# Macro_Pad.net
KiCad netlist of a schematic drawn in EasyEDA Pro
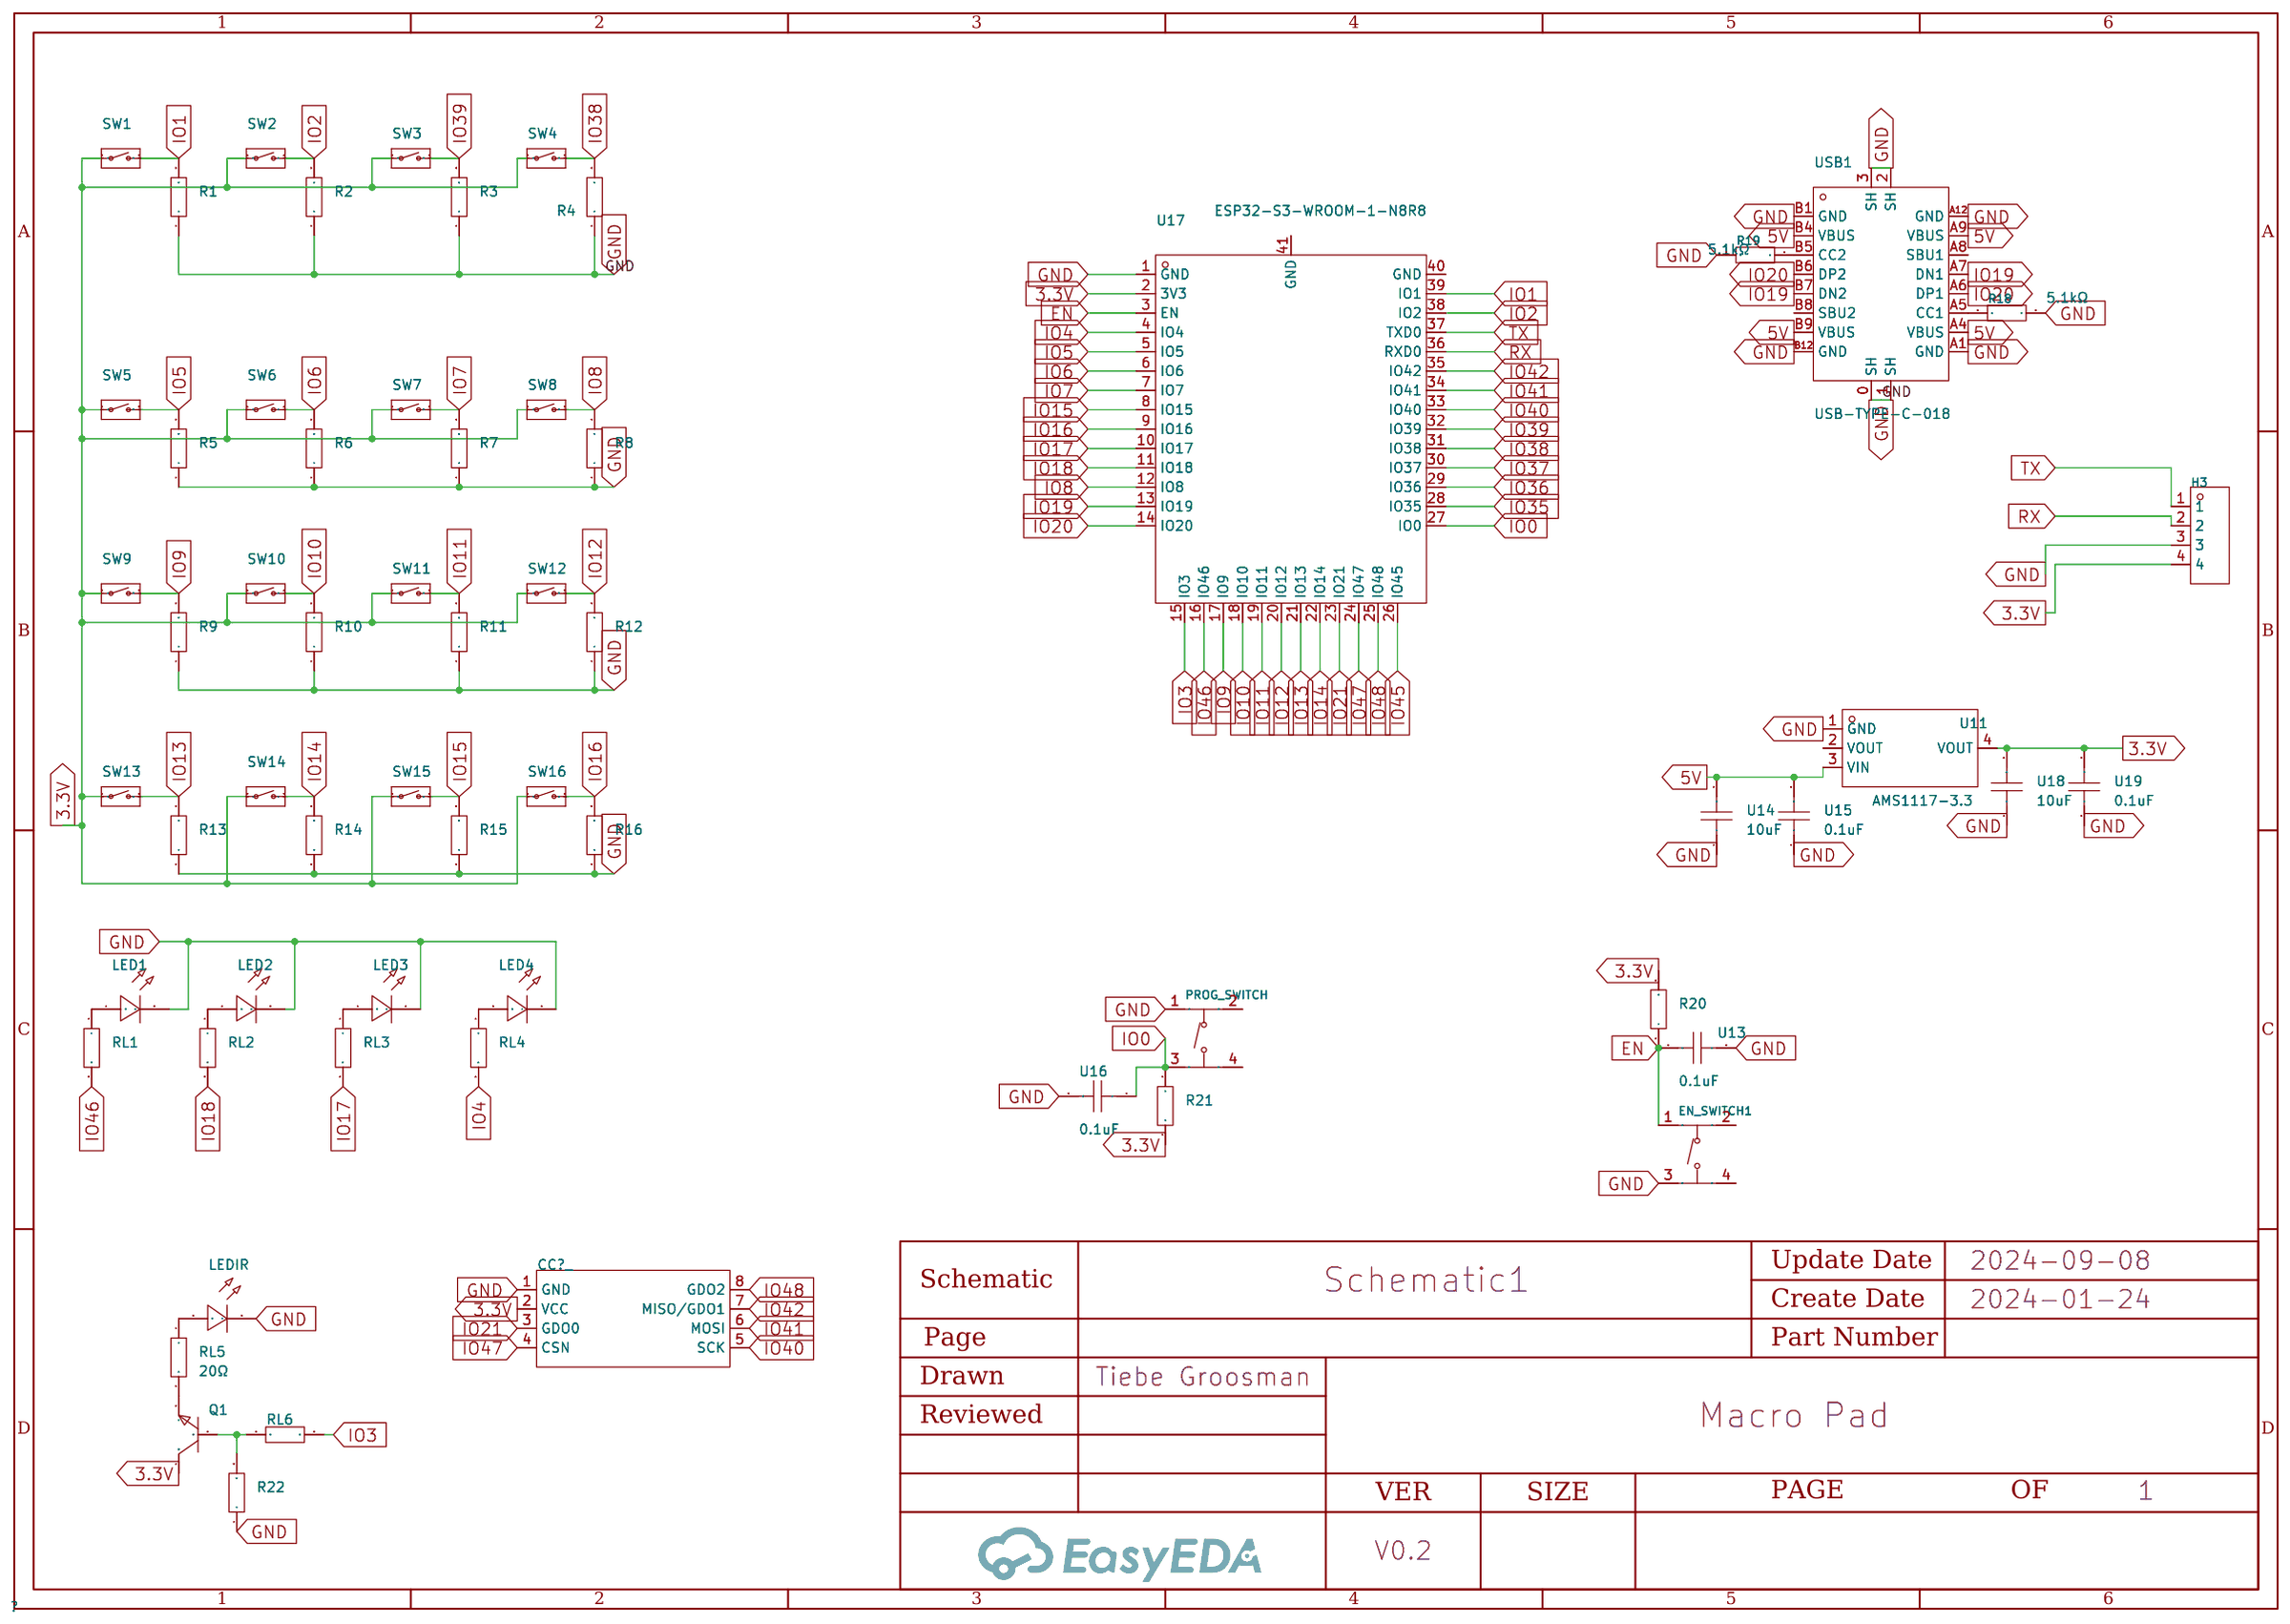
[diagram p0: schematic sheet]

(export (version "E")
  (design (tool "Eeschema 10.0.6"))
  (components
    (comp (ref "CC?_")
      (value "~")
      (footprint "easyedapro:CC1101-BOARS")
      (libsource (lib "easyedapro") (part "CC1101 Module"))
    )
    (comp (ref "EN_SWITCH1")
      (value "TS-1187A-B-A-B")
      (footprint "easyedapro:SW-SMD_4P-L5.1-W5.1-P3.70-LS6.5-TL-2")
      (fields (field (name "Manufacturer") "XKB Connectivity(中国星坤)"))
      (libsource (lib "easyedapro") (part "TS-1187A-B-A-B"))
    )
    (comp (ref "H3")
      (value "~")
      (footprint "easyedapro:HDR-TH_4P-P2.54-V-M")
      (libsource (lib "easyedapro") (part "PZ254V-11-04P"))
    )
    (comp (ref "LED1")
      (value "~")
      (footprint "easyedapro:LED-TH_BD3.0-P2.54-FD")
      (libsource (lib "easyedapro") (part "LED_TH-R"))
    )
    (comp (ref "LED2")
      (value "~")
      (footprint "easyedapro:LED-TH_BD3.0-P2.54-FD")
      (libsource (lib "easyedapro") (part "LED_TH-R"))
    )
    (comp (ref "LED3")
      (value "~")
      (footprint "easyedapro:LED-TH_BD3.0-P2.54-FD")
      (libsource (lib "easyedapro") (part "LED_TH-R"))
    )
    (comp (ref "LED4")
      (value "~")
      (footprint "easyedapro:LED-TH_BD3.0-P2.54-FD")
      (libsource (lib "easyedapro") (part "LED_TH-R"))
    )
    (comp (ref "LEDIR")
      (value "~")
      (footprint "easyedapro:LED-TH_BD3.0-P2.54-FD")
      (libsource (lib "easyedapro") (part "LED_TH-R"))
    )
    (comp (ref "PROG_SWITCH")
      (value "TS-1187A-B-A-B")
      (footprint "easyedapro:SW-SMD_4P-L5.1-W5.1-P3.70-LS6.5-TL-2")
      (fields (field (name "Manufacturer") "XKB Connectivity(中国星坤)"))
      (libsource (lib "easyedapro") (part "TS-1187A-B-A-B"))
    )
    (comp (ref "Q1")
      (value "~")
      (footprint "easyedapro:SOT-23_L2.9-W1.3-P1.90-LS2.4-BR")
      (libsource (lib "easyedapro") (part "NPN"))
    )
    (comp (ref "R1")
      (value "10.2kΩ")
      (footprint "easyedapro:R0402")
      (fields
        (field (name "Manufacturer Part") "0402WGF1022TCE")
        (field (name "Manufacturer") "UNI-ROYAL(厚声)")
      )
      (libsource (lib "easyedapro") (part "0402WGF1022TCE"))
    )
    (comp (ref "R2")
      (value "10.2kΩ")
      (footprint "easyedapro:R0402")
      (fields
        (field (name "Manufacturer Part") "0402WGF1022TCE")
        (field (name "Manufacturer") "UNI-ROYAL(厚声)")
      )
      (libsource (lib "easyedapro") (part "0402WGF1022TCE"))
    )
    (comp (ref "R3")
      (value "10.2kΩ")
      (footprint "easyedapro:R0402")
      (fields
        (field (name "Manufacturer Part") "0402WGF1022TCE")
        (field (name "Manufacturer") "UNI-ROYAL(厚声)")
      )
      (libsource (lib "easyedapro") (part "0402WGF1022TCE"))
    )
    (comp (ref "R4")
      (value "10.2kΩ")
      (footprint "easyedapro:R0402")
      (fields
        (field (name "Manufacturer Part") "0402WGF1022TCE")
        (field (name "Manufacturer") "UNI-ROYAL(厚声)")
      )
      (libsource (lib "easyedapro") (part "0402WGF1022TCE"))
    )
    (comp (ref "R5")
      (value "10.2kΩ")
      (footprint "easyedapro:R0402")
      (fields
        (field (name "Manufacturer Part") "0402WGF1022TCE")
        (field (name "Manufacturer") "UNI-ROYAL(厚声)")
      )
      (libsource (lib "easyedapro") (part "0402WGF1022TCE"))
    )
    (comp (ref "R6")
      (value "10.2kΩ")
      (footprint "easyedapro:R0402")
      (fields
        (field (name "Manufacturer Part") "0402WGF1022TCE")
        (field (name "Manufacturer") "UNI-ROYAL(厚声)")
      )
      (libsource (lib "easyedapro") (part "0402WGF1022TCE"))
    )
    (comp (ref "R7")
      (value "10.2kΩ")
      (footprint "easyedapro:R0402")
      (fields
        (field (name "Manufacturer Part") "0402WGF1022TCE")
        (field (name "Manufacturer") "UNI-ROYAL(厚声)")
      )
      (libsource (lib "easyedapro") (part "0402WGF1022TCE"))
    )
    (comp (ref "R8")
      (value "10.2kΩ")
      (footprint "easyedapro:R0402")
      (fields
        (field (name "Manufacturer Part") "0402WGF1022TCE")
        (field (name "Manufacturer") "UNI-ROYAL(厚声)")
      )
      (libsource (lib "easyedapro") (part "0402WGF1022TCE"))
    )
    (comp (ref "R9")
      (value "10.2kΩ")
      (footprint "easyedapro:R0402")
      (fields
        (field (name "Manufacturer Part") "0402WGF1022TCE")
        (field (name "Manufacturer") "UNI-ROYAL(厚声)")
      )
      (libsource (lib "easyedapro") (part "0402WGF1022TCE"))
    )
    (comp (ref "R10")
      (value "10.2kΩ")
      (footprint "easyedapro:R0402")
      (fields
        (field (name "Manufacturer Part") "0402WGF1022TCE")
        (field (name "Manufacturer") "UNI-ROYAL(厚声)")
      )
      (libsource (lib "easyedapro") (part "0402WGF1022TCE"))
    )
    (comp (ref "R11")
      (value "10.2kΩ")
      (footprint "easyedapro:R0402")
      (fields
        (field (name "Manufacturer Part") "0402WGF1022TCE")
        (field (name "Manufacturer") "UNI-ROYAL(厚声)")
      )
      (libsource (lib "easyedapro") (part "0402WGF1022TCE"))
    )
    (comp (ref "R12")
      (value "10.2kΩ")
      (footprint "easyedapro:R0402")
      (fields
        (field (name "Manufacturer Part") "0402WGF1022TCE")
        (field (name "Manufacturer") "UNI-ROYAL(厚声)")
      )
      (libsource (lib "easyedapro") (part "0402WGF1022TCE"))
    )
    (comp (ref "R13")
      (value "10.2kΩ")
      (footprint "easyedapro:R0402")
      (fields
        (field (name "Manufacturer Part") "0402WGF1022TCE")
        (field (name "Manufacturer") "UNI-ROYAL(厚声)")
      )
      (libsource (lib "easyedapro") (part "0402WGF1022TCE"))
    )
    (comp (ref "R14")
      (value "10.2kΩ")
      (footprint "easyedapro:R0402")
      (fields
        (field (name "Manufacturer Part") "0402WGF1022TCE")
        (field (name "Manufacturer") "UNI-ROYAL(厚声)")
      )
      (libsource (lib "easyedapro") (part "0402WGF1022TCE"))
    )
    (comp (ref "R15")
      (value "10.2kΩ")
      (footprint "easyedapro:R0402")
      (fields
        (field (name "Manufacturer Part") "0402WGF1022TCE")
        (field (name "Manufacturer") "UNI-ROYAL(厚声)")
      )
      (libsource (lib "easyedapro") (part "0402WGF1022TCE"))
    )
    (comp (ref "R16")
      (value "10.2kΩ")
      (footprint "easyedapro:R0402")
      (fields
        (field (name "Manufacturer Part") "0402WGF1022TCE")
        (field (name "Manufacturer") "UNI-ROYAL(厚声)")
      )
      (libsource (lib "easyedapro") (part "0402WGF1022TCE"))
    )
    (comp (ref "R18")
      (value "5.1kΩ")
      (footprint "easyedapro:R0402")
      (fields (field (name "Manufacturer Part") "SCR1210J5K1") (field (name "Manufacturer") "VO(翔胜)"))
      (libsource (lib "easyedapro") (part "0402WGJ0512TCE"))
    )
    (comp (ref "R19")
      (value "5.1kΩ")
      (footprint "easyedapro:R0402")
      (fields (field (name "Manufacturer Part") "SCR1210J5K1") (field (name "Manufacturer") "VO(翔胜)"))
      (libsource (lib "easyedapro") (part "0402WGJ0512TCE"))
    )
    (comp (ref "R20")
      (value "10.2kΩ")
      (footprint "easyedapro:R0402")
      (fields
        (field (name "Manufacturer Part") "0402WGF1022TCE")
        (field (name "Manufacturer") "UNI-ROYAL(厚声)")
      )
      (libsource (lib "easyedapro") (part "0402WGF1022TCE"))
    )
    (comp (ref "R21")
      (value "10.2kΩ")
      (footprint "easyedapro:R0402")
      (fields
        (field (name "Manufacturer Part") "0402WGF1022TCE")
        (field (name "Manufacturer") "UNI-ROYAL(厚声)")
      )
      (libsource (lib "easyedapro") (part "0402WGF1022TCE"))
    )
    (comp (ref "R22")
      (value "10.2kΩ")
      (footprint "easyedapro:R0402")
      (fields
        (field (name "Manufacturer Part") "0402WGF1022TCE")
        (field (name "Manufacturer") "UNI-ROYAL(厚声)")
      )
      (libsource (lib "easyedapro") (part "0402WGF1022TCE"))
    )
    (comp (ref "RL1")
      (value "330Ω")
      (footprint "easyedapro:R0402")
      (fields
        (field (name "Manufacturer Part") "0402WGJ0331TCE")
        (field (name "Manufacturer") "UNI-ROYAL(厚声)")
      )
      (libsource (lib "easyedapro") (part "0402WGJ0331TCE"))
    )
    (comp (ref "RL2")
      (value "330Ω")
      (footprint "easyedapro:R0402")
      (fields
        (field (name "Manufacturer Part") "0402WGJ0331TCE")
        (field (name "Manufacturer") "UNI-ROYAL(厚声)")
      )
      (libsource (lib "easyedapro") (part "0402WGJ0331TCE"))
    )
    (comp (ref "RL3")
      (value "330Ω")
      (footprint "easyedapro:R0402")
      (fields
        (field (name "Manufacturer Part") "0402WGJ0331TCE")
        (field (name "Manufacturer") "UNI-ROYAL(厚声)")
      )
      (libsource (lib "easyedapro") (part "0402WGJ0331TCE"))
    )
    (comp (ref "RL4")
      (value "330Ω")
      (footprint "easyedapro:R0402")
      (fields
        (field (name "Manufacturer Part") "0402WGJ0331TCE")
        (field (name "Manufacturer") "UNI-ROYAL(厚声)")
      )
      (libsource (lib "easyedapro") (part "0402WGJ0331TCE"))
    )
    (comp (ref "RL5")
      (value "20Ω")
      (footprint "easyedapro:R0402")
      (fields
        (field (name "Manufacturer Part") "0402WGJ0331TCE")
        (field (name "Manufacturer") "UNI-ROYAL(厚声)")
      )
      (libsource (lib "easyedapro") (part "0402WGJ0331TCE"))
    )
    (comp (ref "RL6")
      (value "330Ω")
      (footprint "easyedapro:R0402")
      (fields
        (field (name "Manufacturer Part") "0402WGJ0331TCE")
        (field (name "Manufacturer") "UNI-ROYAL(厚声)")
      )
      (libsource (lib "easyedapro") (part "0402WGJ0331TCE"))
    )
    (comp (ref "SW1")
      (value "CHERRY-MX-LED")
      (footprint "easyedapro:CHERRYMX")
      (fields (field (name "Manufacturer Part") "Cherry MX Green") (field (name "Manufacturer") "Cherry"))
      (libsource (lib "easyedapro") (part "CHERRY-MX-LED"))
    )
    (comp (ref "SW2")
      (value "CHERRY-MX-LED")
      (footprint "easyedapro:CHERRYMX")
      (fields (field (name "Manufacturer Part") "Cherry MX Green") (field (name "Manufacturer") "Cherry"))
      (libsource (lib "easyedapro") (part "CHERRY-MX-LED"))
    )
    (comp (ref "SW3")
      (value "CHERRY-MX-LED")
      (footprint "easyedapro:CHERRYMX")
      (fields (field (name "Manufacturer Part") "Cherry MX Green") (field (name "Manufacturer") "Cherry"))
      (libsource (lib "easyedapro") (part "CHERRY-MX-LED"))
    )
    (comp (ref "SW4")
      (value "CHERRY-MX-LED")
      (footprint "easyedapro:CHERRYMX")
      (fields (field (name "Manufacturer Part") "Cherry MX Green") (field (name "Manufacturer") "Cherry"))
      (libsource (lib "easyedapro") (part "CHERRY-MX-LED"))
    )
    (comp (ref "SW5")
      (value "CHERRY-MX-LED")
      (footprint "easyedapro:CHERRYMX")
      (fields (field (name "Manufacturer Part") "Cherry MX Green") (field (name "Manufacturer") "Cherry"))
      (libsource (lib "easyedapro") (part "CHERRY-MX-LED"))
    )
    (comp (ref "SW6")
      (value "CHERRY-MX-LED")
      (footprint "easyedapro:CHERRYMX")
      (fields (field (name "Manufacturer Part") "Cherry MX Green") (field (name "Manufacturer") "Cherry"))
      (libsource (lib "easyedapro") (part "CHERRY-MX-LED"))
    )
    (comp (ref "SW7")
      (value "CHERRY-MX-LED")
      (footprint "easyedapro:CHERRYMX")
      (fields (field (name "Manufacturer Part") "Cherry MX Green") (field (name "Manufacturer") "Cherry"))
      (libsource (lib "easyedapro") (part "CHERRY-MX-LED"))
    )
    (comp (ref "SW8")
      (value "CHERRY-MX-LED")
      (footprint "easyedapro:CHERRYMX")
      (fields (field (name "Manufacturer Part") "Cherry MX Green") (field (name "Manufacturer") "Cherry"))
      (libsource (lib "easyedapro") (part "CHERRY-MX-LED"))
    )
    (comp (ref "SW9")
      (value "CHERRY-MX-LED")
      (footprint "easyedapro:CHERRYMX")
      (fields (field (name "Manufacturer Part") "Cherry MX Green") (field (name "Manufacturer") "Cherry"))
      (libsource (lib "easyedapro") (part "CHERRY-MX-LED"))
    )
    (comp (ref "SW10")
      (value "CHERRY-MX-LED")
      (footprint "easyedapro:CHERRYMX")
      (fields (field (name "Manufacturer Part") "Cherry MX Green") (field (name "Manufacturer") "Cherry"))
      (libsource (lib "easyedapro") (part "CHERRY-MX-LED"))
    )
    (comp (ref "SW11")
      (value "CHERRY-MX-LED")
      (footprint "easyedapro:CHERRYMX")
      (fields (field (name "Manufacturer Part") "Cherry MX Green") (field (name "Manufacturer") "Cherry"))
      (libsource (lib "easyedapro") (part "CHERRY-MX-LED"))
    )
    (comp (ref "SW12")
      (value "CHERRY-MX-LED")
      (footprint "easyedapro:CHERRYMX")
      (fields (field (name "Manufacturer Part") "Cherry MX Green") (field (name "Manufacturer") "Cherry"))
      (libsource (lib "easyedapro") (part "CHERRY-MX-LED"))
    )
    (comp (ref "SW13")
      (value "CHERRY-MX-LED")
      (footprint "easyedapro:CHERRYMX")
      (fields (field (name "Manufacturer Part") "Cherry MX Green") (field (name "Manufacturer") "Cherry"))
      (libsource (lib "easyedapro") (part "CHERRY-MX-LED"))
    )
    (comp (ref "SW14")
      (value "CHERRY-MX-LED")
      (footprint "easyedapro:CHERRYMX")
      (fields (field (name "Manufacturer Part") "Cherry MX Green") (field (name "Manufacturer") "Cherry"))
      (libsource (lib "easyedapro") (part "CHERRY-MX-LED"))
    )
    (comp (ref "SW15")
      (value "CHERRY-MX-LED")
      (footprint "easyedapro:CHERRYMX")
      (fields (field (name "Manufacturer Part") "Cherry MX Green") (field (name "Manufacturer") "Cherry"))
      (libsource (lib "easyedapro") (part "CHERRY-MX-LED"))
    )
    (comp (ref "SW16")
      (value "CHERRY-MX-LED")
      (footprint "easyedapro:CHERRYMX")
      (fields (field (name "Manufacturer Part") "Cherry MX Green") (field (name "Manufacturer") "Cherry"))
      (libsource (lib "easyedapro") (part "CHERRY-MX-LED"))
    )
    (comp (ref "U11")
      (value "AMS1117-3.3")
      (footprint "easyedapro:SOT-223-3_L6.5-W3.4-P2.30-LS7.0-BR")
      (fields (field (name "Manufacturer") "AMS"))
      (libsource (lib "easyedapro") (part "AMS1117-3.3"))
    )
    (comp (ref "U13")
      (value "0.1uF")
      (footprint "easyedapro:C0402")
      (fields
        (field (name "Manufacturer Part") "CC1210KKX7R9BB105")
        (field (name "Manufacturer") "YAGEO(国巨)")
      )
      (libsource (lib "easyedapro") (part "CGA0402X5R105K500GT"))
    )
    (comp (ref "U14")
      (value "10uF")
      (footprint "easyedapro:C0402")
      (fields
        (field (name "Manufacturer Part") "CC1210KKX7R9BB105")
        (field (name "Manufacturer") "YAGEO(国巨)")
      )
      (libsource (lib "easyedapro") (part "CGA0402X5R105K500GT"))
    )
    (comp (ref "U15")
      (value "0.1uF")
      (footprint "easyedapro:C0402")
      (fields
        (field (name "Manufacturer Part") "CC1210KKX7R9BB105")
        (field (name "Manufacturer") "YAGEO(国巨)")
      )
      (libsource (lib "easyedapro") (part "CGA0402X5R105K500GT"))
    )
    (comp (ref "U16")
      (value "0.1uF")
      (footprint "easyedapro:C0402")
      (fields
        (field (name "Manufacturer Part") "CC1210KKX7R9BB105")
        (field (name "Manufacturer") "YAGEO(国巨)")
      )
      (libsource (lib "easyedapro") (part "CGA0402X5R105K500GT"))
    )
    (comp (ref "U17")
      (value "ESP32-S3-WROOM-1-N8R8")
      (footprint "easyedapro:WIRELM-SMD_ESP32-S3-WROOM-1")
      (fields (field (name "Manufacturer") "ESPRESSIF(乐鑫)"))
      (libsource (lib "easyedapro") (part "ESP32-S3-WROOM-1(N8R8)"))
    )
    (comp (ref "U18")
      (value "10uF")
      (footprint "easyedapro:C0402")
      (fields
        (field (name "Manufacturer Part") "CC1210KKX7R9BB105")
        (field (name "Manufacturer") "YAGEO(国巨)")
      )
      (libsource (lib "easyedapro") (part "CGA0402X5R105K500GT"))
    )
    (comp (ref "U19")
      (value "0.1uF")
      (footprint "easyedapro:C0402")
      (fields
        (field (name "Manufacturer Part") "CC1210KKX7R9BB105")
        (field (name "Manufacturer") "YAGEO(国巨)")
      )
      (libsource (lib "easyedapro") (part "CGA0402X5R105K500GT"))
    )
    (comp (ref "USB1")
      (value "USB-TYPE-C-018")
      (footprint "easyedapro:USB-C_SMD-TYPE-C-31-M-12")
      (fields (field (name "Manufacturer") "DEALON(德艺隆)"))
      (libsource (lib "easyedapro") (part "USB-TYPE-C-018"))
    )
  )
  (nets
    (net (code "1") (name "3.3V") (class "Default")
      (node (ref "CC?_") (pin "2") (pinfunction "VCC_2") (pintype "unspecified"))
      (node (ref "H3") (pin "4") (pinfunction "4_4") (pintype "input"))
      (node (ref "Q1") (pin "3") (pinfunction "C_3") (pintype "unspecified"))
      (node (ref "R20") (pin "2") (pinfunction "2_2") (pintype "input"))
      (node (ref "R21") (pin "1") (pinfunction "1_1") (pintype "input"))
      (node (ref "SW1") (pin "1") (pinfunction "1_1") (pintype "unspecified"))
      (node (ref "SW10") (pin "1") (pinfunction "1_1") (pintype "unspecified"))
      (node (ref "SW11") (pin "1") (pinfunction "1_1") (pintype "unspecified"))
      (node (ref "SW12") (pin "1") (pinfunction "1_1") (pintype "unspecified"))
      (node (ref "SW13") (pin "1") (pinfunction "1_1") (pintype "unspecified"))
      (node (ref "SW14") (pin "1") (pinfunction "1_1") (pintype "unspecified"))
      (node (ref "SW15") (pin "1") (pinfunction "1_1") (pintype "unspecified"))
      (node (ref "SW16") (pin "1") (pinfunction "1_1") (pintype "unspecified"))
      (node (ref "SW2") (pin "1") (pinfunction "1_1") (pintype "unspecified"))
      (node (ref "SW3") (pin "1") (pinfunction "1_1") (pintype "unspecified"))
      (node (ref "SW4") (pin "1") (pinfunction "1_1") (pintype "unspecified"))
      (node (ref "SW5") (pin "1") (pinfunction "1_1") (pintype "unspecified"))
      (node (ref "SW6") (pin "1") (pinfunction "1_1") (pintype "unspecified"))
      (node (ref "SW7") (pin "1") (pinfunction "1_1") (pintype "unspecified"))
      (node (ref "SW8") (pin "1") (pinfunction "1_1") (pintype "unspecified"))
      (node (ref "SW9") (pin "1") (pinfunction "1_1") (pintype "unspecified"))
      (node (ref "U11") (pin "4") (pinfunction "VOUT_4") (pintype "unspecified"))
      (node (ref "U17") (pin "2") (pinfunction "3V3_2") (pintype "unspecified"))
      (node (ref "U18") (pin "2") (pinfunction "2_2") (pintype "unspecified"))
      (node (ref "U19") (pin "2") (pinfunction "2_2") (pintype "unspecified"))
    )
    (net (code "2") (name "5V") (class "Default")
      (node (ref "U11") (pin "3") (pinfunction "VIN_3") (pintype "unspecified"))
      (node (ref "U14") (pin "2") (pinfunction "2_2") (pintype "unspecified"))
      (node (ref "U15") (pin "2") (pinfunction "2_2") (pintype "unspecified"))
      (node (ref "USB1") (pin "A4") (pinfunction "VBUS_A4") (pintype "unspecified"))
      (node (ref "USB1") (pin "A9") (pinfunction "VBUS_A9") (pintype "unspecified"))
      (node (ref "USB1") (pin "B4") (pinfunction "VBUS_B4") (pintype "unspecified"))
      (node (ref "USB1") (pin "B9") (pinfunction "VBUS_B9") (pintype "unspecified"))
    )
    (net (code "3") (name "EN") (class "Default")
      (node (ref "EN_SWITCH1") (pin "1") (pinfunction "A_1") (pintype "input"))
      (node (ref "R20") (pin "1") (pinfunction "1_1") (pintype "input"))
      (node (ref "U13") (pin "1") (pinfunction "1_1") (pintype "unspecified"))
      (node (ref "U17") (pin "3") (pinfunction "EN_3") (pintype "unspecified"))
    )
    (net (code "4") (name "GND") (class "Default")
      (node (ref "CC?_") (pin "1") (pinfunction "GND_1") (pintype "unspecified"))
      (node (ref "EN_SWITCH1") (pin "3") (pinfunction "C_3") (pintype "input"))
      (node (ref "H3") (pin "3") (pinfunction "3_3") (pintype "input"))
      (node (ref "LED1") (pin "2") (pinfunction "A_2") (pintype "input"))
      (node (ref "LED2") (pin "2") (pinfunction "A_2") (pintype "input"))
      (node (ref "LED3") (pin "2") (pinfunction "A_2") (pintype "input"))
      (node (ref "LED4") (pin "2") (pinfunction "A_2") (pintype "input"))
      (node (ref "LEDIR") (pin "2") (pinfunction "A_2") (pintype "input"))
      (node (ref "PROG_SWITCH") (pin "1") (pinfunction "A_1") (pintype "input"))
      (node (ref "R1") (pin "1") (pinfunction "1_1") (pintype "input"))
      (node (ref "R10") (pin "1") (pinfunction "1_1") (pintype "input"))
      (node (ref "R11") (pin "1") (pinfunction "1_1") (pintype "input"))
      (node (ref "R12") (pin "1") (pinfunction "1_1") (pintype "input"))
      (node (ref "R13") (pin "1") (pinfunction "1_1") (pintype "input"))
      (node (ref "R14") (pin "1") (pinfunction "1_1") (pintype "input"))
      (node (ref "R15") (pin "1") (pinfunction "1_1") (pintype "input"))
      (node (ref "R16") (pin "1") (pinfunction "1_1") (pintype "input"))
      (node (ref "R18") (pin "1") (pinfunction "1_1") (pintype "input"))
      (node (ref "R19") (pin "1") (pinfunction "1_1") (pintype "input"))
      (node (ref "R2") (pin "1") (pinfunction "1_1") (pintype "input"))
      (node (ref "R22") (pin "1") (pinfunction "1_1") (pintype "input"))
      (node (ref "R3") (pin "1") (pinfunction "1_1") (pintype "input"))
      (node (ref "R4") (pin "1") (pinfunction "1_1") (pintype "input"))
      (node (ref "R5") (pin "1") (pinfunction "1_1") (pintype "input"))
      (node (ref "R6") (pin "1") (pinfunction "1_1") (pintype "input"))
      (node (ref "R7") (pin "1") (pinfunction "1_1") (pintype "input"))
      (node (ref "R8") (pin "1") (pinfunction "1_1") (pintype "input"))
      (node (ref "R9") (pin "1") (pinfunction "1_1") (pintype "input"))
      (node (ref "U11") (pin "1") (pinfunction "GND_1") (pintype "unspecified"))
      (node (ref "U13") (pin "2") (pinfunction "2_2") (pintype "unspecified"))
      (node (ref "U14") (pin "1") (pinfunction "1_1") (pintype "unspecified"))
      (node (ref "U15") (pin "1") (pinfunction "1_1") (pintype "unspecified"))
      (node (ref "U16") (pin "2") (pinfunction "2_2") (pintype "unspecified"))
      (node (ref "U17") (pin "1") (pinfunction "GND_1") (pintype "unspecified"))
      (node (ref "U18") (pin "1") (pinfunction "1_1") (pintype "unspecified"))
      (node (ref "U19") (pin "1") (pinfunction "1_1") (pintype "unspecified"))
      (node (ref "USB1") (pin "0") (pinfunction "SH_0") (pintype "unspecified"))
      (node (ref "USB1") (pin "1") (pinfunction "SH_1") (pintype "unspecified"))
      (node (ref "USB1") (pin "2") (pinfunction "SH_2") (pintype "unspecified"))
      (node (ref "USB1") (pin "3") (pinfunction "SH_3") (pintype "unspecified"))
      (node (ref "USB1") (pin "A1") (pinfunction "GND_A1") (pintype "unspecified"))
      (node (ref "USB1") (pin "A12") (pinfunction "GND_A12") (pintype "unspecified"))
      (node (ref "USB1") (pin "B1") (pinfunction "GND_B1") (pintype "unspecified"))
      (node (ref "USB1") (pin "B12") (pinfunction "GND_B12") (pintype "unspecified"))
    )
    (net (code "5") (name "IO0") (class "Default")
      (node (ref "PROG_SWITCH") (pin "3") (pinfunction "C_3") (pintype "input"))
      (node (ref "R21") (pin "2") (pinfunction "2_2") (pintype "input"))
      (node (ref "U16") (pin "1") (pinfunction "1_1") (pintype "unspecified"))
      (node (ref "U17") (pin "27") (pinfunction "IO0_27") (pintype "unspecified"))
    )
    (net (code "6") (name "IO1") (class "Default")
      (node (ref "R1") (pin "2") (pinfunction "2_2") (pintype "input"))
      (node (ref "SW1") (pin "2") (pinfunction "2_2") (pintype "unspecified"))
      (node (ref "U17") (pin "39") (pinfunction "IO1_39") (pintype "unspecified"))
    )
    (net (code "7") (name "IO2") (class "Default")
      (node (ref "R2") (pin "2") (pinfunction "2_2") (pintype "input"))
      (node (ref "SW2") (pin "2") (pinfunction "2_2") (pintype "unspecified"))
      (node (ref "U17") (pin "38") (pinfunction "IO2_38") (pintype "unspecified"))
    )
    (net (code "8") (name "IO3") (class "Default")
      (node (ref "RL6") (pin "2") (pinfunction "2_2") (pintype "input"))
      (node (ref "U17") (pin "15") (pinfunction "IO3_15") (pintype "unspecified"))
    )
    (net (code "9") (name "IO4") (class "Default")
      (node (ref "RL4") (pin "2") (pinfunction "2_2") (pintype "input"))
      (node (ref "U17") (pin "4") (pinfunction "IO4_4") (pintype "unspecified"))
    )
    (net (code "10") (name "IO5") (class "Default")
      (node (ref "R5") (pin "2") (pinfunction "2_2") (pintype "input"))
      (node (ref "SW5") (pin "2") (pinfunction "2_2") (pintype "unspecified"))
      (node (ref "U17") (pin "5") (pinfunction "IO5_5") (pintype "unspecified"))
    )
    (net (code "11") (name "IO6") (class "Default")
      (node (ref "R6") (pin "2") (pinfunction "2_2") (pintype "input"))
      (node (ref "SW6") (pin "2") (pinfunction "2_2") (pintype "unspecified"))
      (node (ref "U17") (pin "6") (pinfunction "IO6_6") (pintype "unspecified"))
    )
    (net (code "12") (name "IO7") (class "Default")
      (node (ref "R7") (pin "2") (pinfunction "2_2") (pintype "input"))
      (node (ref "SW7") (pin "2") (pinfunction "2_2") (pintype "unspecified"))
      (node (ref "U17") (pin "7") (pinfunction "IO7_7") (pintype "unspecified"))
    )
    (net (code "13") (name "IO8") (class "Default")
      (node (ref "R8") (pin "2") (pinfunction "2_2") (pintype "input"))
      (node (ref "SW8") (pin "2") (pinfunction "2_2") (pintype "unspecified"))
      (node (ref "U17") (pin "12") (pinfunction "IO8_12") (pintype "unspecified"))
    )
    (net (code "14") (name "IO9") (class "Default")
      (node (ref "R9") (pin "2") (pinfunction "2_2") (pintype "input"))
      (node (ref "SW9") (pin "2") (pinfunction "2_2") (pintype "unspecified"))
      (node (ref "U17") (pin "17") (pinfunction "IO9_17") (pintype "unspecified"))
    )
    (net (code "15") (name "IO10") (class "Default")
      (node (ref "R10") (pin "2") (pinfunction "2_2") (pintype "input"))
      (node (ref "SW10") (pin "2") (pinfunction "2_2") (pintype "unspecified"))
      (node (ref "U17") (pin "18") (pinfunction "IO10_18") (pintype "unspecified"))
    )
    (net (code "16") (name "IO11") (class "Default")
      (node (ref "R11") (pin "2") (pinfunction "2_2") (pintype "input"))
      (node (ref "SW11") (pin "2") (pinfunction "2_2") (pintype "unspecified"))
      (node (ref "U17") (pin "19") (pinfunction "IO11_19") (pintype "unspecified"))
    )
    (net (code "17") (name "IO12") (class "Default")
      (node (ref "R12") (pin "2") (pinfunction "2_2") (pintype "input"))
      (node (ref "SW12") (pin "2") (pinfunction "2_2") (pintype "unspecified"))
      (node (ref "U17") (pin "20") (pinfunction "IO12_20") (pintype "unspecified"))
    )
    (net (code "18") (name "IO13") (class "Default")
      (node (ref "R13") (pin "2") (pinfunction "2_2") (pintype "input"))
      (node (ref "SW13") (pin "2") (pinfunction "2_2") (pintype "unspecified"))
      (node (ref "U17") (pin "21") (pinfunction "IO13_21") (pintype "unspecified"))
    )
    (net (code "19") (name "IO14") (class "Default")
      (node (ref "R14") (pin "2") (pinfunction "2_2") (pintype "input"))
      (node (ref "SW14") (pin "2") (pinfunction "2_2") (pintype "unspecified"))
      (node (ref "U17") (pin "22") (pinfunction "IO14_22") (pintype "unspecified"))
    )
    (net (code "20") (name "IO15") (class "Default")
      (node (ref "R15") (pin "2") (pinfunction "2_2") (pintype "input"))
      (node (ref "SW15") (pin "2") (pinfunction "2_2") (pintype "unspecified"))
      (node (ref "U17") (pin "8") (pinfunction "IO15_8") (pintype "unspecified"))
    )
    (net (code "21") (name "IO16") (class "Default")
      (node (ref "R16") (pin "2") (pinfunction "2_2") (pintype "input"))
      (node (ref "SW16") (pin "2") (pinfunction "2_2") (pintype "unspecified"))
      (node (ref "U17") (pin "9") (pinfunction "IO16_9") (pintype "unspecified"))
    )
    (net (code "22") (name "IO17") (class "Default")
      (node (ref "RL3") (pin "2") (pinfunction "2_2") (pintype "input"))
      (node (ref "U17") (pin "10") (pinfunction "IO17_10") (pintype "unspecified"))
    )
    (net (code "23") (name "IO18") (class "Default")
      (node (ref "RL2") (pin "2") (pinfunction "2_2") (pintype "input"))
      (node (ref "U17") (pin "11") (pinfunction "IO18_11") (pintype "unspecified"))
    )
    (net (code "24") (name "IO19") (class "Default")
      (node (ref "U17") (pin "13") (pinfunction "IO19_13") (pintype "unspecified"))
      (node (ref "USB1") (pin "A7") (pinfunction "DN1_A7") (pintype "unspecified"))
      (node (ref "USB1") (pin "B7") (pinfunction "DN2_B7") (pintype "unspecified"))
    )
    (net (code "25") (name "IO20") (class "Default")
      (node (ref "U17") (pin "14") (pinfunction "IO20_14") (pintype "unspecified"))
      (node (ref "USB1") (pin "A6") (pinfunction "DP1_A6") (pintype "unspecified"))
      (node (ref "USB1") (pin "B6") (pinfunction "DP2_B6") (pintype "unspecified"))
    )
    (net (code "26") (name "IO21") (class "Default")
      (node (ref "CC?_") (pin "3") (pinfunction "GDO0_3") (pintype "unspecified"))
      (node (ref "U17") (pin "23") (pinfunction "IO21_23") (pintype "unspecified"))
    )
    (net (code "27") (name "IO35") (class "Default")
      (node (ref "U17") (pin "28") (pinfunction "IO35_28") (pintype "unspecified"))
    )
    (net (code "28") (name "IO36") (class "Default")
      (node (ref "U17") (pin "29") (pinfunction "IO36_29") (pintype "unspecified"))
    )
    (net (code "29") (name "IO37") (class "Default")
      (node (ref "U17") (pin "30") (pinfunction "IO37_30") (pintype "unspecified"))
    )
    (net (code "30") (name "IO38") (class "Default")
      (node (ref "R4") (pin "2") (pinfunction "2_2") (pintype "input"))
      (node (ref "SW4") (pin "2") (pinfunction "2_2") (pintype "unspecified"))
      (node (ref "U17") (pin "31") (pinfunction "IO38_31") (pintype "unspecified"))
    )
    (net (code "31") (name "IO39") (class "Default")
      (node (ref "R3") (pin "2") (pinfunction "2_2") (pintype "input"))
      (node (ref "SW3") (pin "2") (pinfunction "2_2") (pintype "unspecified"))
      (node (ref "U17") (pin "32") (pinfunction "IO39_32") (pintype "unspecified"))
    )
    (net (code "32") (name "IO40") (class "Default")
      (node (ref "CC?_") (pin "5") (pinfunction "SCK_5") (pintype "unspecified"))
      (node (ref "U17") (pin "33") (pinfunction "IO40_33") (pintype "unspecified"))
    )
    (net (code "33") (name "IO41") (class "Default")
      (node (ref "CC?_") (pin "6") (pinfunction "MOSI_6") (pintype "unspecified"))
      (node (ref "U17") (pin "34") (pinfunction "IO41_34") (pintype "unspecified"))
    )
    (net (code "34") (name "IO42") (class "Default")
      (node (ref "CC?_") (pin "7") (pinfunction "MISO/GDO1_7") (pintype "unspecified"))
      (node (ref "U17") (pin "35") (pinfunction "IO42_35") (pintype "unspecified"))
    )
    (net (code "35") (name "IO45") (class "Default")
      (node (ref "U17") (pin "26") (pinfunction "IO45_26") (pintype "unspecified"))
    )
    (net (code "36") (name "IO46") (class "Default")
      (node (ref "RL1") (pin "2") (pinfunction "2_2") (pintype "input"))
      (node (ref "U17") (pin "16") (pinfunction "IO46_16") (pintype "unspecified"))
    )
    (net (code "37") (name "IO47") (class "Default")
      (node (ref "CC?_") (pin "4") (pinfunction "CSN_4") (pintype "unspecified"))
      (node (ref "U17") (pin "24") (pinfunction "IO47_24") (pintype "unspecified"))
    )
    (net (code "38") (name "IO48") (class "Default")
      (node (ref "CC?_") (pin "8") (pinfunction "GDO2_8") (pintype "unspecified"))
      (node (ref "U17") (pin "25") (pinfunction "IO48_25") (pintype "unspecified"))
    )
    (net (code "39") (name "Net-(LED1-C)") (class "Default")
      (node (ref "LED1") (pin "1") (pinfunction "C_1") (pintype "input"))
      (node (ref "RL1") (pin "1") (pinfunction "1_1") (pintype "input"))
    )
    (net (code "40") (name "Net-(LED2-C)") (class "Default")
      (node (ref "LED2") (pin "1") (pinfunction "C_1") (pintype "input"))
      (node (ref "RL2") (pin "1") (pinfunction "1_1") (pintype "input"))
    )
    (net (code "41") (name "Net-(LED3-C)") (class "Default")
      (node (ref "LED3") (pin "1") (pinfunction "C_1") (pintype "input"))
      (node (ref "RL3") (pin "1") (pinfunction "1_1") (pintype "input"))
    )
    (net (code "42") (name "Net-(LED4-C)") (class "Default")
      (node (ref "LED4") (pin "1") (pinfunction "C_1") (pintype "input"))
      (node (ref "RL4") (pin "1") (pinfunction "1_1") (pintype "input"))
    )
    (net (code "43") (name "Net-(LEDIR-C)") (class "Default")
      (node (ref "LEDIR") (pin "1") (pinfunction "C_1") (pintype "input"))
      (node (ref "RL5") (pin "1") (pinfunction "1_1") (pintype "input"))
    )
    (net (code "44") (name "Net-(Q1-B)") (class "Default")
      (node (ref "Q1") (pin "1") (pinfunction "B_1") (pintype "unspecified"))
      (node (ref "R22") (pin "2") (pinfunction "2_2") (pintype "input"))
      (node (ref "RL6") (pin "1") (pinfunction "1_1") (pintype "input"))
    )
    (net (code "45") (name "Net-(Q1-E)") (class "Default")
      (node (ref "Q1") (pin "2") (pinfunction "E_2") (pintype "unspecified"))
      (node (ref "RL5") (pin "2") (pinfunction "2_2") (pintype "input"))
    )
    (net (code "46") (name "Net-(USB1-CC1)") (class "Default")
      (node (ref "R18") (pin "2") (pinfunction "2_2") (pintype "input"))
      (node (ref "USB1") (pin "A5") (pinfunction "CC1_A5") (pintype "unspecified"))
    )
    (net (code "47") (name "Net-(USB1-CC2)") (class "Default")
      (node (ref "R19") (pin "2") (pinfunction "2_2") (pintype "input"))
      (node (ref "USB1") (pin "B5") (pinfunction "CC2_B5") (pintype "unspecified"))
    )
    (net (code "48") (name "RX") (class "Default")
      (node (ref "H3") (pin "2") (pinfunction "2_2") (pintype "input"))
      (node (ref "U17") (pin "36") (pinfunction "RXD0_36") (pintype "unspecified"))
    )
    (net (code "49") (name "TX") (class "Default")
      (node (ref "H3") (pin "1") (pinfunction "1_1") (pintype "input"))
      (node (ref "U17") (pin "37") (pinfunction "TXD0_37") (pintype "unspecified"))
    )
    (net (code "50") (name "unconnected-(EN_SWITCH1-B-Pad2)") (class "Default")
      (node (ref "EN_SWITCH1") (pin "2") (pinfunction "B_2") (pintype "input"))
    )
    (net (code "51") (name "unconnected-(EN_SWITCH1-D-Pad4)") (class "Default")
      (node (ref "EN_SWITCH1") (pin "4") (pinfunction "D_4") (pintype "input"))
    )
    (net (code "52") (name "unconnected-(PROG_SWITCH-B-Pad2)") (class "Default")
      (node (ref "PROG_SWITCH") (pin "2") (pinfunction "B_2") (pintype "input"))
    )
    (net (code "53") (name "unconnected-(PROG_SWITCH-D-Pad4)") (class "Default")
      (node (ref "PROG_SWITCH") (pin "4") (pinfunction "D_4") (pintype "input"))
    )
    (net (code "54") (name "unconnected-(U11-VOUT-Pad2)") (class "Default")
      (node (ref "U11") (pin "2") (pinfunction "VOUT_2") (pintype "unspecified"))
    )
    (net (code "55") (name "unconnected-(U17-GND-Pad40)") (class "Default")
      (node (ref "U17") (pin "40") (pinfunction "GND_40") (pintype "unspecified"))
    )
    (net (code "56") (name "unconnected-(U17-GND-Pad41)") (class "Default")
      (node (ref "U17") (pin "41") (pinfunction "GND_41") (pintype "unspecified"))
    )
    (net (code "57") (name "unconnected-(USB1-SBU1-PadA8)") (class "Default")
      (node (ref "USB1") (pin "A8") (pinfunction "SBU1_A8") (pintype "unspecified"))
    )
    (net (code "58") (name "unconnected-(USB1-SBU2-PadB8)") (class "Default")
      (node (ref "USB1") (pin "B8") (pinfunction "SBU2_B8") (pintype "unspecified"))
    )
  )
)
